# sch.net
KiCad netlist of a schematic drawn in Altium Designer
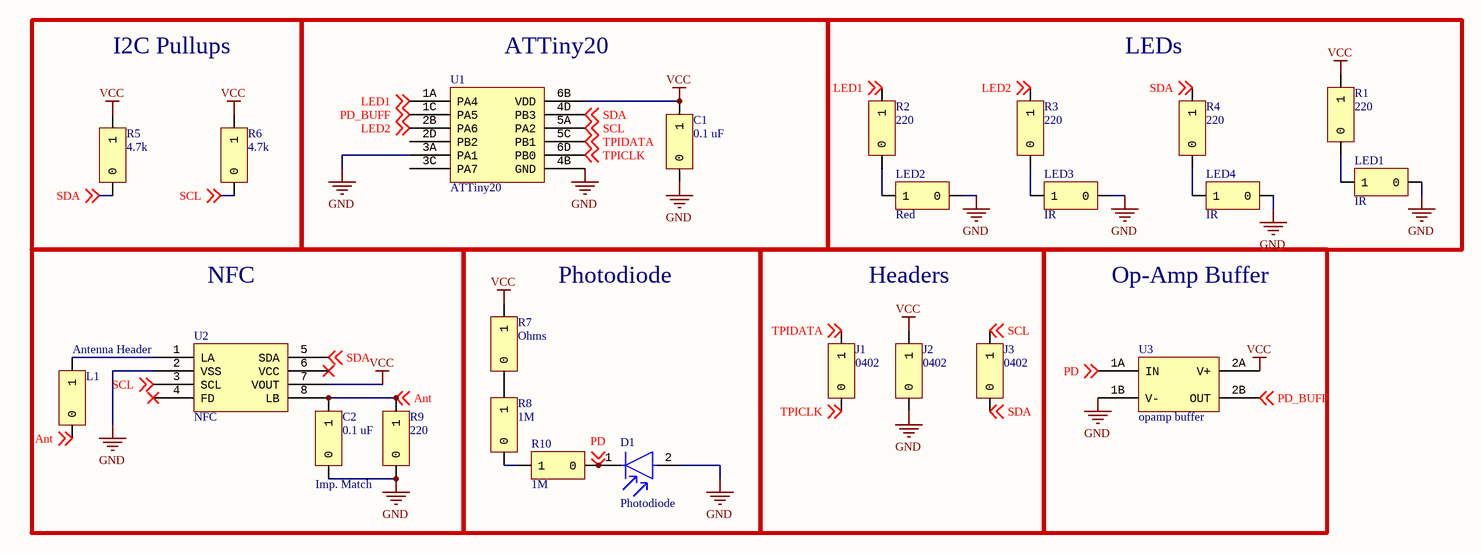
[diagram p0: sch.SchDoc]

(export (version "E")
  (design (tool "Eeschema 10.0.6"))
  (components
    (comp (ref "C1")
      (value "0.1 uF")
      (footprint "01005")
      (description "01005 Component")
      (fields (field (name "MPN") "CL02A104KQ2NNNC"))
      (libsource (lib "schlib") (part "01005"))
    )
    (comp (ref "C2")
      (value "0.1 uF")
      (footprint "01005")
      (description "01005 Component")
      (fields (field (name "MPN") "CL02A104KQ2NNNC"))
      (libsource (lib "schlib") (part "01005"))
    )
    (comp (ref "D1")
      (value "Photodiode")
      (footprint "FP-6_541-5064_01-4-MFG")
      (description "0805 PHOTODIODE\r\ntemd7000x01")
      (fields
        (field (name "MANUFACTURER") "Vishay")
        (field (name "OCTOPART") "https://octopart.com/temd6200fx01-vishay-19158932")
      )
      (libsource (lib "Altium Content Vault") (part "9b7c99953c265a88c20b8f1023d9605"))
    )
    (comp (ref "J1")
      (value "0402")
      (footprint "0402")
      (description "0402 Component")
      (libsource (lib "schlib") (part "0402"))
    )
    (comp (ref "J2")
      (value "0402")
      (footprint "0402")
      (description "0402 Component")
      (libsource (lib "schlib") (part "0402"))
    )
    (comp (ref "J3")
      (value "0402")
      (footprint "0402")
      (description "0402 Component")
      (libsource (lib "schlib") (part "0402"))
    )
    (comp (ref "L1")
      (value "Antenna Header")
      (footprint "0402")
      (description "0402 Component")
      (libsource (lib "schlib") (part "0402"))
    )
    (comp (ref "LED1")
      (value "IR")
      (footprint "0402")
      (description "0402 Component\r\nSFH 4043")
      (fields (field (name "MPN") "SFH 4043"))
      (libsource (lib "") (part "0402_1"))
    )
    (comp (ref "LED2")
      (value "Red")
      (footprint "0201")
      (description "0201 Component\r\nXZMDR155W")
      (fields (field (name "MPN") "XZMDR155W"))
      (libsource (lib "schlib") (part "0201"))
    )
    (comp (ref "LED3")
      (value "IR")
      (footprint "0402")
      (description "0402 Component\r\nSFH 4043")
      (fields (field (name "MPN") "SFH 4043"))
      (libsource (lib "") (part "0402_1"))
    )
    (comp (ref "LED4")
      (value "IR")
      (footprint "0402")
      (description "0402 Component\r\nSFH 4043")
      (fields (field (name "MPN") "SFH 4043"))
      (libsource (lib "") (part "0402_1"))
    )
    (comp (ref "R1")
      (value "220")
      (footprint "01005")
      (description "01005 Component\r\nCRCW0100220RFREL")
      (fields (field (name "MPN") "CRCW0100220RFREL"))
      (libsource (lib "schlib") (part "01005"))
    )
    (comp (ref "R2")
      (value "220")
      (footprint "01005")
      (description "01005 Component\r\nCRCW0100220RFREL")
      (fields (field (name "MPN") "CRCW0100220RFREL"))
      (libsource (lib "schlib") (part "01005"))
    )
    (comp (ref "R3")
      (value "220")
      (footprint "01005")
      (description "01005 Component\r\nCRCW0100220RFREL")
      (fields (field (name "MPN") "CRCW0100220RFREL"))
      (libsource (lib "schlib") (part "01005"))
    )
    (comp (ref "R4")
      (value "220")
      (footprint "01005")
      (description "01005 Component\r\nCRCW0100220RFREL")
      (fields (field (name "MPN") "CRCW0100220RFREL"))
      (libsource (lib "schlib") (part "01005"))
    )
    (comp (ref "R5")
      (value "4.7k")
      (footprint "01005")
      (description "01005 Component")
      (fields (field (name "MPN") "CL02A104KQ2NNNC"))
      (libsource (lib "schlib") (part "01005"))
    )
    (comp (ref "R6")
      (value "4.7k")
      (footprint "01005")
      (description "01005 Component")
      (fields (field (name "MPN") "CL02A104KQ2NNNC"))
      (libsource (lib "schlib") (part "01005"))
    )
    (comp (ref "R7")
      (value "Ohms")
      (footprint "01005")
      (description "01005 Component\r\nCRCW01001M00FREL\r\n<Placeholder if more gain is necessary>")
      (fields (field (name "MPN") "CRCW01001M00FREL"))
      (libsource (lib "schlib") (part "01005"))
    )
    (comp (ref "R8")
      (value "1M")
      (footprint "01005")
      (description "01005 Component\r\nCRCW01001M00FREL")
      (fields (field (name "MPN") "CRCW01001M00FREL"))
      (libsource (lib "schlib") (part "01005"))
    )
    (comp (ref "R9")
      (value "220")
      (footprint "01005")
      (description "01005 Component\r\nCRCW0100220RFREL")
      (fields (field (name "MPN") "CRCW0100220RFREL"))
      (libsource (lib "schlib") (part "01005"))
    )
    (comp (ref "R10")
      (value "1M")
      (footprint "01005")
      (description "01005 Component\r\nCRCW01001M00FREL")
      (fields (field (name "MPN") "CRCW01001M00FREL"))
      (libsource (lib "") (part "01005_1"))
    )
    (comp (ref "U1")
      (value "ATTiny20")
      (footprint "Large_attiny")
      (libsource (lib "schlib") (part "ATTiny20"))
    )
    (comp (ref "U2") (value "NFC") (footprint "NFC") (libsource (lib "schlib") (part "NFC")))
    (comp (ref "U3") (value "opamp buffer") (footprint "opamp") (libsource (lib "schlib") (part "Op-amp")))
  )
  (nets
    (net (code "1") (name "Ant") (class "Default")
      (node (ref "C2") (pin "1") (pinfunction "1_1") (pintype "passive"))
      (node (ref "L1") (pin "0") (pinfunction "0_0") (pintype "passive"))
      (node (ref "R9") (pin "1") (pinfunction "1_1") (pintype "passive"))
      (node (ref "U2") (pin "8") (pinfunction "LB_8") (pintype "passive"))
    )
    (net (code "2") (name "GND") (class "Default")
      (node (ref "C1") (pin "0") (pinfunction "0_0") (pintype "passive"))
      (node (ref "C2") (pin "0") (pinfunction "0_0") (pintype "passive"))
      (node (ref "D1") (pin "2") (pinfunction "A_2") (pintype "passive"))
      (node (ref "J2") (pin "0") (pinfunction "0_0") (pintype "passive"))
      (node (ref "LED1") (pin "0") (pinfunction "0_0") (pintype "passive"))
      (node (ref "LED2") (pin "0") (pinfunction "0_0") (pintype "passive"))
      (node (ref "LED3") (pin "0") (pinfunction "0_0") (pintype "passive"))
      (node (ref "LED4") (pin "0") (pinfunction "0_0") (pintype "passive"))
      (node (ref "R9") (pin "0") (pinfunction "0_0") (pintype "passive"))
      (node (ref "U1") (pin "3A") (pinfunction "PA1_3A") (pintype "passive"))
      (node (ref "U1") (pin "4B") (pinfunction "GND_4B") (pintype "passive"))
      (node (ref "U2") (pin "2") (pinfunction "VSS_2") (pintype "passive"))
      (node (ref "U3") (pin "1B") (pinfunction "V-_1B") (pintype "passive"))
    )
    (net (code "3") (name "LED1") (class "Default")
      (node (ref "R2") (pin "1") (pinfunction "1_1") (pintype "passive"))
      (node (ref "U1") (pin "1A") (pinfunction "PA4_1A") (pintype "passive"))
    )
    (net (code "4") (name "LED2") (class "Default")
      (node (ref "R3") (pin "1") (pinfunction "1_1") (pintype "passive"))
      (node (ref "U1") (pin "2B") (pinfunction "PA6_2B") (pintype "passive"))
    )
    (net (code "5") (name "Net-(LED1-Pad1)") (class "Default")
      (node (ref "LED1") (pin "1") (pinfunction "1_1") (pintype "passive"))
      (node (ref "R1") (pin "0") (pinfunction "0_0") (pintype "passive"))
    )
    (net (code "6") (name "Net-(LED2-Pad1)") (class "Default")
      (node (ref "LED2") (pin "1") (pinfunction "1_1") (pintype "passive"))
      (node (ref "R2") (pin "0") (pinfunction "0_0") (pintype "passive"))
    )
    (net (code "7") (name "Net-(LED3-Pad1)") (class "Default")
      (node (ref "LED3") (pin "1") (pinfunction "1_1") (pintype "passive"))
      (node (ref "R3") (pin "0") (pinfunction "0_0") (pintype "passive"))
    )
    (net (code "8") (name "Net-(LED4-Pad1)") (class "Default")
      (node (ref "LED4") (pin "1") (pinfunction "1_1") (pintype "passive"))
      (node (ref "R4") (pin "0") (pinfunction "0_0") (pintype "passive"))
    )
    (net (code "9") (name "Net-(R7-Pad0)") (class "Default")
      (node (ref "R7") (pin "0") (pinfunction "0_0") (pintype "passive"))
      (node (ref "R8") (pin "1") (pinfunction "1_1") (pintype "passive"))
    )
    (net (code "10") (name "Net-(R10-Pad1)") (class "Default")
      (node (ref "R10") (pin "1") (pinfunction "1_1") (pintype "passive"))
      (node (ref "R8") (pin "0") (pinfunction "0_0") (pintype "passive"))
    )
    (net (code "11") (name "Net-(U2-LA)") (class "Default")
      (node (ref "L1") (pin "1") (pinfunction "1_1") (pintype "passive"))
      (node (ref "U2") (pin "1") (pinfunction "LA_1") (pintype "passive"))
    )
    (net (code "12") (name "PD") (class "Default")
      (node (ref "D1") (pin "1") (pinfunction "C_1") (pintype "passive"))
      (node (ref "R10") (pin "0") (pinfunction "0_0") (pintype "passive"))
      (node (ref "U3") (pin "1A") (pinfunction "IN_1A") (pintype "passive"))
    )
    (net (code "13") (name "PD_BUFF") (class "Default")
      (node (ref "U1") (pin "1C") (pinfunction "PA5_1C") (pintype "passive"))
      (node (ref "U3") (pin "2B") (pinfunction "OUT_2B") (pintype "passive"))
    )
    (net (code "14") (name "SCL") (class "Default")
      (node (ref "J3") (pin "1") (pinfunction "1_1") (pintype "passive"))
      (node (ref "R6") (pin "0") (pinfunction "0_0") (pintype "passive"))
      (node (ref "U1") (pin "5A") (pinfunction "PA2_5A") (pintype "passive"))
      (node (ref "U2") (pin "3") (pinfunction "SCL_3") (pintype "passive"))
    )
    (net (code "15") (name "SDA") (class "Default")
      (node (ref "J3") (pin "0") (pinfunction "0_0") (pintype "passive"))
      (node (ref "R4") (pin "1") (pinfunction "1_1") (pintype "passive"))
      (node (ref "R5") (pin "0") (pinfunction "0_0") (pintype "passive"))
      (node (ref "U1") (pin "4D") (pinfunction "PB3_4D") (pintype "passive"))
      (node (ref "U2") (pin "5") (pinfunction "SDA_5") (pintype "passive"))
    )
    (net (code "16") (name "TPICLK") (class "Default")
      (node (ref "J1") (pin "0") (pinfunction "0_0") (pintype "passive"))
      (node (ref "U1") (pin "6D") (pinfunction "PB0_6D") (pintype "passive"))
    )
    (net (code "17") (name "TPIDATA") (class "Default")
      (node (ref "J1") (pin "1") (pinfunction "1_1") (pintype "passive"))
      (node (ref "U1") (pin "5C") (pinfunction "PB1_5C") (pintype "passive"))
    )
    (net (code "18") (name "VCC") (class "Default")
      (node (ref "C1") (pin "1") (pinfunction "1_1") (pintype "passive"))
      (node (ref "J2") (pin "1") (pinfunction "1_1") (pintype "passive"))
      (node (ref "R1") (pin "1") (pinfunction "1_1") (pintype "passive"))
      (node (ref "R5") (pin "1") (pinfunction "1_1") (pintype "passive"))
      (node (ref "R6") (pin "1") (pinfunction "1_1") (pintype "passive"))
      (node (ref "R7") (pin "1") (pinfunction "1_1") (pintype "passive"))
      (node (ref "U1") (pin "6B") (pinfunction "VDD_6B") (pintype "passive"))
      (node (ref "U2") (pin "7") (pinfunction "VOUT_7") (pintype "passive"))
      (node (ref "U3") (pin "2A") (pinfunction "V+_2A") (pintype "passive"))
    )
    (net (code "19") (name "unconnected-(U1-PA7-Pad3C)") (class "Default")
      (node (ref "U1") (pin "3C") (pinfunction "PA7_3C") (pintype "passive"))
    )
    (net (code "20") (name "unconnected-(U1-PB2-Pad2D)") (class "Default")
      (node (ref "U1") (pin "2D") (pinfunction "PB2_2D") (pintype "passive"))
    )
    (net (code "21") (name "unconnected-(U2-FD-Pad4)") (class "Default")
      (node (ref "U2") (pin "4") (pinfunction "FD_4") (pintype "passive+no_connect"))
    )
    (net (code "22") (name "unconnected-(U2-VCC-Pad6)") (class "Default")
      (node (ref "U2") (pin "6") (pinfunction "VCC_6") (pintype "passive+no_connect"))
    )
  )
)
